# rf12socket5.net
KiCad netlist of a schematic drawn in EAGLE
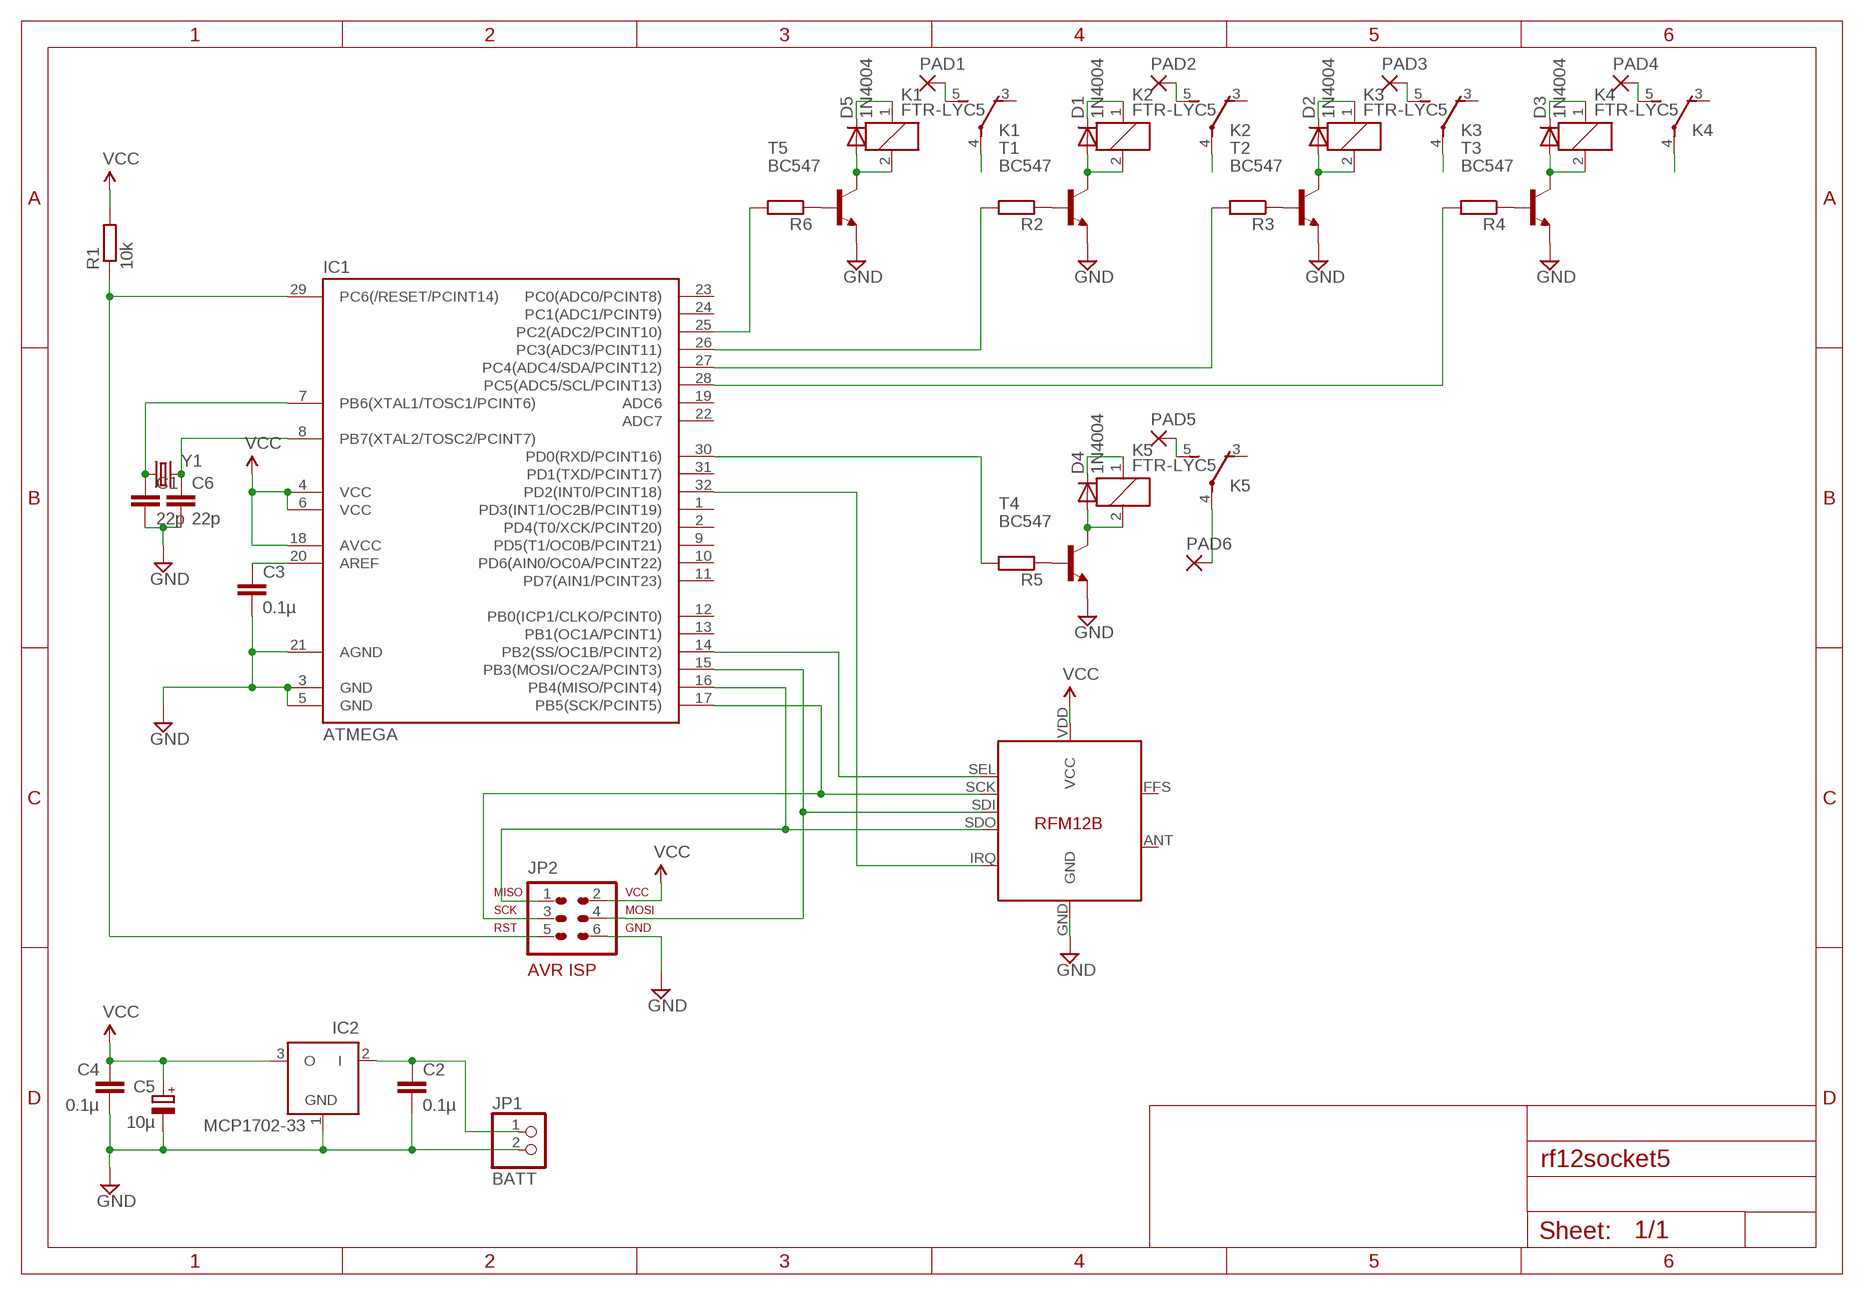
[diagram p0: schematic, sheet 1]

(export (version "E")
  (design (tool "Eeschema 10.0.6"))
  (components
    (comp (ref "C1")
      (value "22p")
      (footprint "eagle-import:CAP-PTH-SMALL")
      (libsource (lib "eagle-import") (part "CAPPTH"))
    )
    (comp (ref "C2")
      (value "0.1µ")
      (footprint "eagle-import:0805")
      (libsource (lib "eagle-import") (part "CAP0805"))
    )
    (comp (ref "C3")
      (value "0.1µ")
      (footprint "eagle-import:0805")
      (libsource (lib "eagle-import") (part "CAP0805"))
    )
    (comp (ref "C4")
      (value "0.1µ")
      (footprint "eagle-import:0805")
      (libsource (lib "eagle-import") (part "CAP0805"))
    )
    (comp (ref "C5")
      (value "10µ")
      (footprint "eagle-import:E2,5-7")
      (libsource (lib "eagle-import") (part "CPOL-EUE2.5-7"))
    )
    (comp (ref "C6")
      (value "22p")
      (footprint "eagle-import:CAP-PTH-SMALL")
      (libsource (lib "eagle-import") (part "CAPPTH"))
    )
    (comp (ref "D1")
      (value "1N4004")
      (footprint "eagle-import:DO41-10")
      (libsource (lib "eagle-import") (part "1N4004"))
    )
    (comp (ref "D2")
      (value "1N4004")
      (footprint "eagle-import:DO41-10")
      (libsource (lib "eagle-import") (part "1N4004"))
    )
    (comp (ref "D3")
      (value "1N4004")
      (footprint "eagle-import:DO41-10")
      (libsource (lib "eagle-import") (part "1N4004"))
    )
    (comp (ref "D4")
      (value "1N4004")
      (footprint "eagle-import:DO41-10")
      (libsource (lib "eagle-import") (part "1N4004"))
    )
    (comp (ref "D5")
      (value "1N4004")
      (footprint "eagle-import:DO41-10")
      (libsource (lib "eagle-import") (part "1N4004"))
    )
    (comp (ref "IC1")
      (value "ATMEGA")
      (footprint "eagle-import:TQFP32-08")
      (libsource (lib "eagle-import") (part "MEGA48/88/168-AU"))
    )
    (comp (ref "IC2")
      (value "MCP1702-33")
      (footprint "eagle-import:TO92")
      (libsource (lib "eagle-import") (part "MCP1702Z"))
    )
    (comp (ref "JP1")
      (value "BATT")
      (footprint "eagle-import:1X02")
      (libsource (lib "eagle-import") (part "PINHD-1X2"))
    )
    (comp (ref "JP2")
      (value "AVR-ISP-6VERT")
      (footprint "eagle-import:AVR-ISP-6")
      (libsource (lib "eagle-import") (part "AVR-ISP-6VERT"))
    )
    (comp (ref "K1")
      (value "FTR-LYC5")
      (footprint "eagle-import:FTR-LYC")
      (libsource (lib "eagle-import") (part "FTR-LYC5"))
    )
    (comp (ref "K2")
      (value "FTR-LYC5")
      (footprint "eagle-import:FTR-LYC")
      (libsource (lib "eagle-import") (part "FTR-LYC5"))
    )
    (comp (ref "K3")
      (value "FTR-LYC5")
      (footprint "eagle-import:FTR-LYC")
      (libsource (lib "eagle-import") (part "FTR-LYC5"))
    )
    (comp (ref "K4")
      (value "FTR-LYC5")
      (footprint "eagle-import:FTR-LYC")
      (libsource (lib "eagle-import") (part "FTR-LYC5"))
    )
    (comp (ref "K5")
      (value "FTR-LYC5")
      (footprint "eagle-import:FTR-LYC")
      (libsource (lib "eagle-import") (part "FTR-LYC5"))
    )
    (comp (ref "PAD1")
      (value "SMD5")
      (footprint "eagle-import:SMD2,54-5,08")
      (libsource (lib "eagle-import") (part "SMD5"))
    )
    (comp (ref "PAD2")
      (value "SMD5")
      (footprint "eagle-import:SMD2,54-5,08")
      (libsource (lib "eagle-import") (part "SMD5"))
    )
    (comp (ref "PAD3")
      (value "SMD5")
      (footprint "eagle-import:SMD2,54-5,08")
      (libsource (lib "eagle-import") (part "SMD5"))
    )
    (comp (ref "PAD4")
      (value "SMD5")
      (footprint "eagle-import:SMD2,54-5,08")
      (libsource (lib "eagle-import") (part "SMD5"))
    )
    (comp (ref "PAD5")
      (value "SMD5")
      (footprint "eagle-import:SMD2,54-5,08")
      (libsource (lib "eagle-import") (part "SMD5"))
    )
    (comp (ref "PAD6")
      (value "SMD5")
      (footprint "eagle-import:SMD2,54-5,08")
      (libsource (lib "eagle-import") (part "SMD5"))
    )
    (comp (ref "R1")
      (value "10k")
      (footprint "eagle-import:0207_10")
      (libsource (lib "eagle-import") (part "R-EU_0207/10"))
    )
    (comp (ref "R2")
      (value "R-EU_0207/10")
      (footprint "eagle-import:0207_10")
      (libsource (lib "eagle-import") (part "R-EU_0207/10"))
    )
    (comp (ref "R3")
      (value "R-EU_0207/10")
      (footprint "eagle-import:0207_10")
      (libsource (lib "eagle-import") (part "R-EU_0207/10"))
    )
    (comp (ref "R4")
      (value "R-EU_0207/10")
      (footprint "eagle-import:0207_10")
      (libsource (lib "eagle-import") (part "R-EU_0207/10"))
    )
    (comp (ref "R5")
      (value "R-EU_0207/10")
      (footprint "eagle-import:0207_10")
      (libsource (lib "eagle-import") (part "R-EU_0207/10"))
    )
    (comp (ref "R6")
      (value "R-EU_0207/10")
      (footprint "eagle-import:0207_10")
      (libsource (lib "eagle-import") (part "R-EU_0207/10"))
    )
    (comp (ref "T1")
      (value "BC547")
      (footprint "eagle-import:TO92")
      (libsource (lib "eagle-import") (part "BC547"))
    )
    (comp (ref "T2")
      (value "BC547")
      (footprint "eagle-import:TO92")
      (libsource (lib "eagle-import") (part "BC547"))
    )
    (comp (ref "T3")
      (value "BC547")
      (footprint "eagle-import:TO92")
      (libsource (lib "eagle-import") (part "BC547"))
    )
    (comp (ref "T4")
      (value "BC547")
      (footprint "eagle-import:TO92")
      (libsource (lib "eagle-import") (part "BC547"))
    )
    (comp (ref "T5")
      (value "BC547")
      (footprint "eagle-import:TO92")
      (libsource (lib "eagle-import") (part "BC547"))
    )
    (comp (ref "U$1")
      (value "RFM12B")
      (footprint "eagle-import:RFM12B")
      (libsource (lib "eagle-import") (part "RFM12B"))
    )
    (comp (ref "Y1")
      (value "CRYSTALHC49US")
      (footprint "eagle-import:HC49US")
      (libsource (lib "eagle-import") (part "CRYSTALHC49US"))
    )
  )
  (nets
    (net (code "1") (name "/L230V") (class "Default")
      (node (ref "K1") (pin "4") (pinfunction "P_4") (pintype "passive"))
      (node (ref "K2") (pin "4") (pinfunction "P_4") (pintype "passive"))
      (node (ref "K3") (pin "4") (pinfunction "P_4") (pintype "passive"))
      (node (ref "K4") (pin "4") (pinfunction "P_4") (pintype "passive"))
      (node (ref "K5") (pin "4") (pinfunction "P_4") (pintype "passive"))
      (node (ref "PAD6") (pin "1") (pinfunction "P_1") (pintype "passive"))
    )
    (net (code "2") (name "/PWR") (class "Default")
      (node (ref "C2") (pin "1") (pinfunction "1_1") (pintype "passive"))
      (node (ref "D1") (pin "C") (pinfunction "C_C") (pintype "passive"))
      (node (ref "D2") (pin "C") (pinfunction "C_C") (pintype "passive"))
      (node (ref "D3") (pin "C") (pinfunction "C_C") (pintype "passive"))
      (node (ref "D4") (pin "C") (pinfunction "C_C") (pintype "passive"))
      (node (ref "D5") (pin "C") (pinfunction "C_C") (pintype "passive"))
      (node (ref "IC2") (pin "2") (pinfunction "I_2") (pintype "input"))
      (node (ref "JP1") (pin "1") (pinfunction "1_1") (pintype "passive"))
      (node (ref "K1") (pin "1") (pinfunction "1_1") (pintype "passive"))
      (node (ref "K2") (pin "1") (pinfunction "1_1") (pintype "passive"))
      (node (ref "K3") (pin "1") (pinfunction "1_1") (pintype "passive"))
      (node (ref "K4") (pin "1") (pinfunction "1_1") (pintype "passive"))
      (node (ref "K5") (pin "1") (pinfunction "1_1") (pintype "passive"))
    )
    (net (code "3") (name "GND") (class "Default")
      (node (ref "C1") (pin "2") (pinfunction "2_2") (pintype "passive"))
      (node (ref "C2") (pin "2") (pinfunction "2_2") (pintype "passive"))
      (node (ref "C3") (pin "2") (pinfunction "2_2") (pintype "passive"))
      (node (ref "C4") (pin "2") (pinfunction "2_2") (pintype "passive"))
      (node (ref "C5") (pin "-") (pinfunction "-_-") (pintype "passive"))
      (node (ref "C6") (pin "2") (pinfunction "2_2") (pintype "passive"))
      (node (ref "IC1") (pin "21") (pinfunction "AGND_21") (pintype "power_in"))
      (node (ref "IC1") (pin "3") (pinfunction "GND_3") (pintype "power_in"))
      (node (ref "IC1") (pin "5") (pinfunction "GND_5") (pintype "power_in"))
      (node (ref "IC2") (pin "1") (pinfunction "GND_1") (pintype "power_in"))
      (node (ref "JP1") (pin "2") (pinfunction "2_2") (pintype "passive"))
      (node (ref "JP2") (pin "6") (pinfunction "6_6") (pintype "passive"))
      (node (ref "T1") (pin "1") (pinfunction "E_1") (pintype "passive"))
      (node (ref "T2") (pin "1") (pinfunction "E_1") (pintype "passive"))
      (node (ref "T3") (pin "1") (pinfunction "E_1") (pintype "passive"))
      (node (ref "T4") (pin "1") (pinfunction "E_1") (pintype "passive"))
      (node (ref "T5") (pin "1") (pinfunction "E_1") (pintype "passive"))
      (node (ref "U$1") (pin "GND") (pinfunction "GND_GND") (pintype "power_in"))
    )
    (net (code "4") (name "Net-(IC1-AREF)") (class "Default")
      (node (ref "C3") (pin "1") (pinfunction "1_1") (pintype "passive"))
      (node (ref "IC1") (pin "20") (pinfunction "AREF_20") (pintype "passive"))
    )
    (net (code "5") (name "Net-(IC1-PB2(SS{slash}OC1B{slash}PCINT2))") (class "Default")
      (node (ref "IC1") (pin "14") (pinfunction "PB2(SS/OC1B/PCINT2)_14") (pintype "bidirectional"))
      (node (ref "U$1") (pin "SEL") (pinfunction "SEL_SEL") (pintype "input"))
    )
    (net (code "6") (name "Net-(IC1-PB3(MOSI{slash}OC2A{slash}PCINT3))") (class "Default")
      (node (ref "IC1") (pin "15") (pinfunction "PB3(MOSI/OC2A/PCINT3)_15") (pintype "bidirectional"))
      (node (ref "JP2") (pin "4") (pinfunction "4_4") (pintype "passive"))
      (node (ref "U$1") (pin "SDI") (pinfunction "SDI_SDI") (pintype "input"))
    )
    (net (code "7") (name "Net-(IC1-PB4(MISO{slash}PCINT4))") (class "Default")
      (node (ref "IC1") (pin "16") (pinfunction "PB4(MISO/PCINT4)_16") (pintype "bidirectional"))
      (node (ref "JP2") (pin "1") (pinfunction "1_1") (pintype "passive"))
      (node (ref "U$1") (pin "SDO") (pinfunction "SDO_SDO") (pintype "output"))
    )
    (net (code "8") (name "Net-(IC1-PB5(SCK{slash}PCINT5))") (class "Default")
      (node (ref "IC1") (pin "17") (pinfunction "PB5(SCK/PCINT5)_17") (pintype "bidirectional"))
      (node (ref "JP2") (pin "3") (pinfunction "3_3") (pintype "passive"))
      (node (ref "U$1") (pin "SCK") (pinfunction "SCK_SCK") (pintype "input"))
    )
    (net (code "9") (name "Net-(IC1-PB6(XTAL1{slash}TOSC1{slash}PCINT6))") (class "Default")
      (node (ref "C1") (pin "1") (pinfunction "1_1") (pintype "passive"))
      (node (ref "IC1") (pin "7") (pinfunction "PB6(XTAL1/TOSC1/PCINT6)_7") (pintype "bidirectional"))
      (node (ref "Y1") (pin "1") (pinfunction "1_1") (pintype "passive"))
    )
    (net (code "10") (name "Net-(IC1-PB7(XTAL2{slash}TOSC2{slash}PCINT7))") (class "Default")
      (node (ref "C6") (pin "1") (pinfunction "1_1") (pintype "passive"))
      (node (ref "IC1") (pin "8") (pinfunction "PB7(XTAL2/TOSC2/PCINT7)_8") (pintype "bidirectional"))
      (node (ref "Y1") (pin "2") (pinfunction "2_2") (pintype "passive"))
    )
    (net (code "11") (name "Net-(IC1-PC2(ADC2{slash}PCINT10))") (class "Default")
      (node (ref "IC1") (pin "25") (pinfunction "PC2(ADC2/PCINT10)_25") (pintype "bidirectional"))
      (node (ref "R6") (pin "2") (pinfunction "2_2") (pintype "passive"))
    )
    (net (code "12") (name "Net-(IC1-PC3(ADC3{slash}PCINT11))") (class "Default")
      (node (ref "IC1") (pin "26") (pinfunction "PC3(ADC3/PCINT11)_26") (pintype "bidirectional"))
      (node (ref "R2") (pin "2") (pinfunction "2_2") (pintype "passive"))
    )
    (net (code "13") (name "Net-(IC1-PC4(ADC4{slash}SDA{slash}PCINT12))") (class "Default")
      (node (ref "IC1") (pin "27") (pinfunction "PC4(ADC4/SDA/PCINT12)_27") (pintype "bidirectional"))
      (node (ref "R3") (pin "2") (pinfunction "2_2") (pintype "passive"))
    )
    (net (code "14") (name "Net-(IC1-PC5(ADC5{slash}SCL{slash}PCINT13))") (class "Default")
      (node (ref "IC1") (pin "28") (pinfunction "PC5(ADC5/SCL/PCINT13)_28") (pintype "bidirectional"))
      (node (ref "R4") (pin "2") (pinfunction "2_2") (pintype "passive"))
    )
    (net (code "15") (name "Net-(IC1-PC6({slash}RESET{slash}PCINT14))") (class "Default")
      (node (ref "IC1") (pin "29") (pinfunction "PC6(/RESET/PCINT14)_29") (pintype "bidirectional"))
      (node (ref "JP2") (pin "5") (pinfunction "5_5") (pintype "passive"))
      (node (ref "R1") (pin "1") (pinfunction "1_1") (pintype "passive"))
    )
    (net (code "16") (name "Net-(IC1-PD0(RXD{slash}PCINT16))") (class "Default")
      (node (ref "IC1") (pin "30") (pinfunction "PD0(RXD/PCINT16)_30") (pintype "bidirectional"))
      (node (ref "R5") (pin "2") (pinfunction "2_2") (pintype "passive"))
    )
    (net (code "17") (name "Net-(IC1-PD2(INT0{slash}PCINT18))") (class "Default")
      (node (ref "IC1") (pin "32") (pinfunction "PD2(INT0/PCINT18)_32") (pintype "bidirectional"))
      (node (ref "U$1") (pin "IRQ") (pinfunction "IRQ_IRQ") (pintype "open_collector"))
    )
    (net (code "18") (name "Net-(K1A-S)") (class "Default")
      (node (ref "K1") (pin "5") (pinfunction "S_5") (pintype "passive"))
      (node (ref "PAD1") (pin "1") (pinfunction "P_1") (pintype "passive"))
    )
    (net (code "19") (name "Net-(K2A-S)") (class "Default")
      (node (ref "K2") (pin "5") (pinfunction "S_5") (pintype "passive"))
      (node (ref "PAD2") (pin "1") (pinfunction "P_1") (pintype "passive"))
    )
    (net (code "20") (name "Net-(K3A-S)") (class "Default")
      (node (ref "K3") (pin "5") (pinfunction "S_5") (pintype "passive"))
      (node (ref "PAD3") (pin "1") (pinfunction "P_1") (pintype "passive"))
    )
    (net (code "21") (name "Net-(K4A-S)") (class "Default")
      (node (ref "K4") (pin "5") (pinfunction "S_5") (pintype "passive"))
      (node (ref "PAD4") (pin "1") (pinfunction "P_1") (pintype "passive"))
    )
    (net (code "22") (name "Net-(K5A-S)") (class "Default")
      (node (ref "K5") (pin "5") (pinfunction "S_5") (pintype "passive"))
      (node (ref "PAD5") (pin "1") (pinfunction "P_1") (pintype "passive"))
    )
    (net (code "23") (name "Net-(T1-B)") (class "Default")
      (node (ref "R2") (pin "1") (pinfunction "1_1") (pintype "passive"))
      (node (ref "T1") (pin "2") (pinfunction "B_2") (pintype "passive"))
    )
    (net (code "24") (name "Net-(T1-C)") (class "Default")
      (node (ref "D1") (pin "A") (pinfunction "A_A") (pintype "passive"))
      (node (ref "K2") (pin "2") (pinfunction "2_2") (pintype "passive"))
      (node (ref "T1") (pin "3") (pinfunction "C_3") (pintype "passive"))
    )
    (net (code "25") (name "Net-(T2-B)") (class "Default")
      (node (ref "R3") (pin "1") (pinfunction "1_1") (pintype "passive"))
      (node (ref "T2") (pin "2") (pinfunction "B_2") (pintype "passive"))
    )
    (net (code "26") (name "Net-(T2-C)") (class "Default")
      (node (ref "D2") (pin "A") (pinfunction "A_A") (pintype "passive"))
      (node (ref "K3") (pin "2") (pinfunction "2_2") (pintype "passive"))
      (node (ref "T2") (pin "3") (pinfunction "C_3") (pintype "passive"))
    )
    (net (code "27") (name "Net-(T3-B)") (class "Default")
      (node (ref "R4") (pin "1") (pinfunction "1_1") (pintype "passive"))
      (node (ref "T3") (pin "2") (pinfunction "B_2") (pintype "passive"))
    )
    (net (code "28") (name "Net-(T3-C)") (class "Default")
      (node (ref "D3") (pin "A") (pinfunction "A_A") (pintype "passive"))
      (node (ref "K4") (pin "2") (pinfunction "2_2") (pintype "passive"))
      (node (ref "T3") (pin "3") (pinfunction "C_3") (pintype "passive"))
    )
    (net (code "29") (name "Net-(T4-B)") (class "Default")
      (node (ref "R5") (pin "1") (pinfunction "1_1") (pintype "passive"))
      (node (ref "T4") (pin "2") (pinfunction "B_2") (pintype "passive"))
    )
    (net (code "30") (name "Net-(T4-C)") (class "Default")
      (node (ref "D4") (pin "A") (pinfunction "A_A") (pintype "passive"))
      (node (ref "K5") (pin "2") (pinfunction "2_2") (pintype "passive"))
      (node (ref "T4") (pin "3") (pinfunction "C_3") (pintype "passive"))
    )
    (net (code "31") (name "Net-(T5-B)") (class "Default")
      (node (ref "R6") (pin "1") (pinfunction "1_1") (pintype "passive"))
      (node (ref "T5") (pin "2") (pinfunction "B_2") (pintype "passive"))
    )
    (net (code "32") (name "Net-(T5-C)") (class "Default")
      (node (ref "D5") (pin "A") (pinfunction "A_A") (pintype "passive"))
      (node (ref "K1") (pin "2") (pinfunction "2_2") (pintype "passive"))
      (node (ref "T5") (pin "3") (pinfunction "C_3") (pintype "passive"))
    )
    (net (code "33") (name "VCC") (class "Default")
      (node (ref "C4") (pin "1") (pinfunction "1_1") (pintype "passive"))
      (node (ref "C5") (pin "+") (pinfunction "+_+") (pintype "passive"))
      (node (ref "IC1") (pin "18") (pinfunction "AVCC_18") (pintype "passive"))
      (node (ref "IC1") (pin "4") (pinfunction "VCC_4") (pintype "power_in"))
      (node (ref "IC1") (pin "6") (pinfunction "VCC_6") (pintype "power_in"))
      (node (ref "IC2") (pin "3") (pinfunction "O_3") (pintype "input"))
      (node (ref "JP2") (pin "2") (pinfunction "2_2") (pintype "passive"))
      (node (ref "R1") (pin "2") (pinfunction "2_2") (pintype "passive"))
      (node (ref "U$1") (pin "VDD") (pinfunction "VCC_VDD") (pintype "power_in"))
    )
    (net (code "34") (name "unconnected-(IC1-ADC6-Pad19)") (class "Default")
      (node (ref "IC1") (pin "19") (pinfunction "ADC6_19") (pintype "passive"))
    )
    (net (code "35") (name "unconnected-(IC1-ADC7-Pad22)") (class "Default")
      (node (ref "IC1") (pin "22") (pinfunction "ADC7_22") (pintype "passive"))
    )
    (net (code "36") (name "unconnected-(IC1-PB0(ICP1{slash}CLKO{slash}PCINT0)-Pad12)") (class "Default")
      (node (ref "IC1") (pin "12") (pinfunction "PB0(ICP1/CLKO/PCINT0)_12") (pintype "bidirectional"))
    )
    (net (code "37") (name "unconnected-(IC1-PB1(OC1A{slash}PCINT1)-Pad13)") (class "Default")
      (node (ref "IC1") (pin "13") (pinfunction "PB1(OC1A/PCINT1)_13") (pintype "bidirectional"))
    )
    (net (code "38") (name "unconnected-(IC1-PC0(ADC0{slash}PCINT8)-Pad23)") (class "Default")
      (node (ref "IC1") (pin "23") (pinfunction "PC0(ADC0/PCINT8)_23") (pintype "bidirectional"))
    )
    (net (code "39") (name "unconnected-(IC1-PC1(ADC1{slash}PCINT9)-Pad24)") (class "Default")
      (node (ref "IC1") (pin "24") (pinfunction "PC1(ADC1/PCINT9)_24") (pintype "bidirectional"))
    )
    (net (code "40") (name "unconnected-(IC1-PD1(TXD{slash}PCINT17)-Pad31)") (class "Default")
      (node (ref "IC1") (pin "31") (pinfunction "PD1(TXD/PCINT17)_31") (pintype "bidirectional"))
    )
    (net (code "41") (name "unconnected-(IC1-PD3(INT1{slash}OC2B{slash}PCINT19)-Pad1)") (class "Default")
      (node (ref "IC1") (pin "1") (pinfunction "PD3(INT1/OC2B/PCINT19)_1") (pintype "bidirectional"))
    )
    (net (code "42") (name "unconnected-(IC1-PD4(T0{slash}XCK{slash}PCINT20)-Pad2)") (class "Default")
      (node (ref "IC1") (pin "2") (pinfunction "PD4(T0/XCK/PCINT20)_2") (pintype "bidirectional"))
    )
    (net (code "43") (name "unconnected-(IC1-PD5(T1{slash}OC0B{slash}PCINT21)-Pad9)") (class "Default")
      (node (ref "IC1") (pin "9") (pinfunction "PD5(T1/OC0B/PCINT21)_9") (pintype "bidirectional"))
    )
    (net (code "44") (name "unconnected-(IC1-PD6(AIN0{slash}OC0A{slash}PCINT22)-Pad10)") (class "Default")
      (node (ref "IC1") (pin "10") (pinfunction "PD6(AIN0/OC0A/PCINT22)_10") (pintype "bidirectional"))
    )
    (net (code "45") (name "unconnected-(IC1-PD7(AIN1{slash}PCINT23)-Pad11)") (class "Default")
      (node (ref "IC1") (pin "11") (pinfunction "PD7(AIN1/PCINT23)_11") (pintype "bidirectional"))
    )
    (net (code "46") (name "unconnected-(K1A-O-Pad3)") (class "Default")
      (node (ref "K1") (pin "3") (pinfunction "O_3") (pintype "passive"))
    )
    (net (code "47") (name "unconnected-(K2A-O-Pad3)") (class "Default")
      (node (ref "K2") (pin "3") (pinfunction "O_3") (pintype "passive"))
    )
    (net (code "48") (name "unconnected-(K3A-O-Pad3)") (class "Default")
      (node (ref "K3") (pin "3") (pinfunction "O_3") (pintype "passive"))
    )
    (net (code "49") (name "unconnected-(K4A-O-Pad3)") (class "Default")
      (node (ref "K4") (pin "3") (pinfunction "O_3") (pintype "passive"))
    )
    (net (code "50") (name "unconnected-(K5A-O-Pad3)") (class "Default")
      (node (ref "K5") (pin "3") (pinfunction "O_3") (pintype "passive"))
    )
    (net (code "51") (name "unconnected-(U$1-PadANT)") (class "Default")
      (node (ref "U$1") (pin "ANT") (pinfunction "ANT_ANT") (pintype "passive"))
    )
    (net (code "52") (name "unconnected-(U$1-PadFFS)") (class "Default")
      (node (ref "U$1") (pin "FFS") (pinfunction "FFS_FFS") (pintype "bidirectional"))
    )
  )
)
